# TIDA-010933-DCDC-HVGAN.net
KiCad netlist of a schematic drawn in Altium Designer
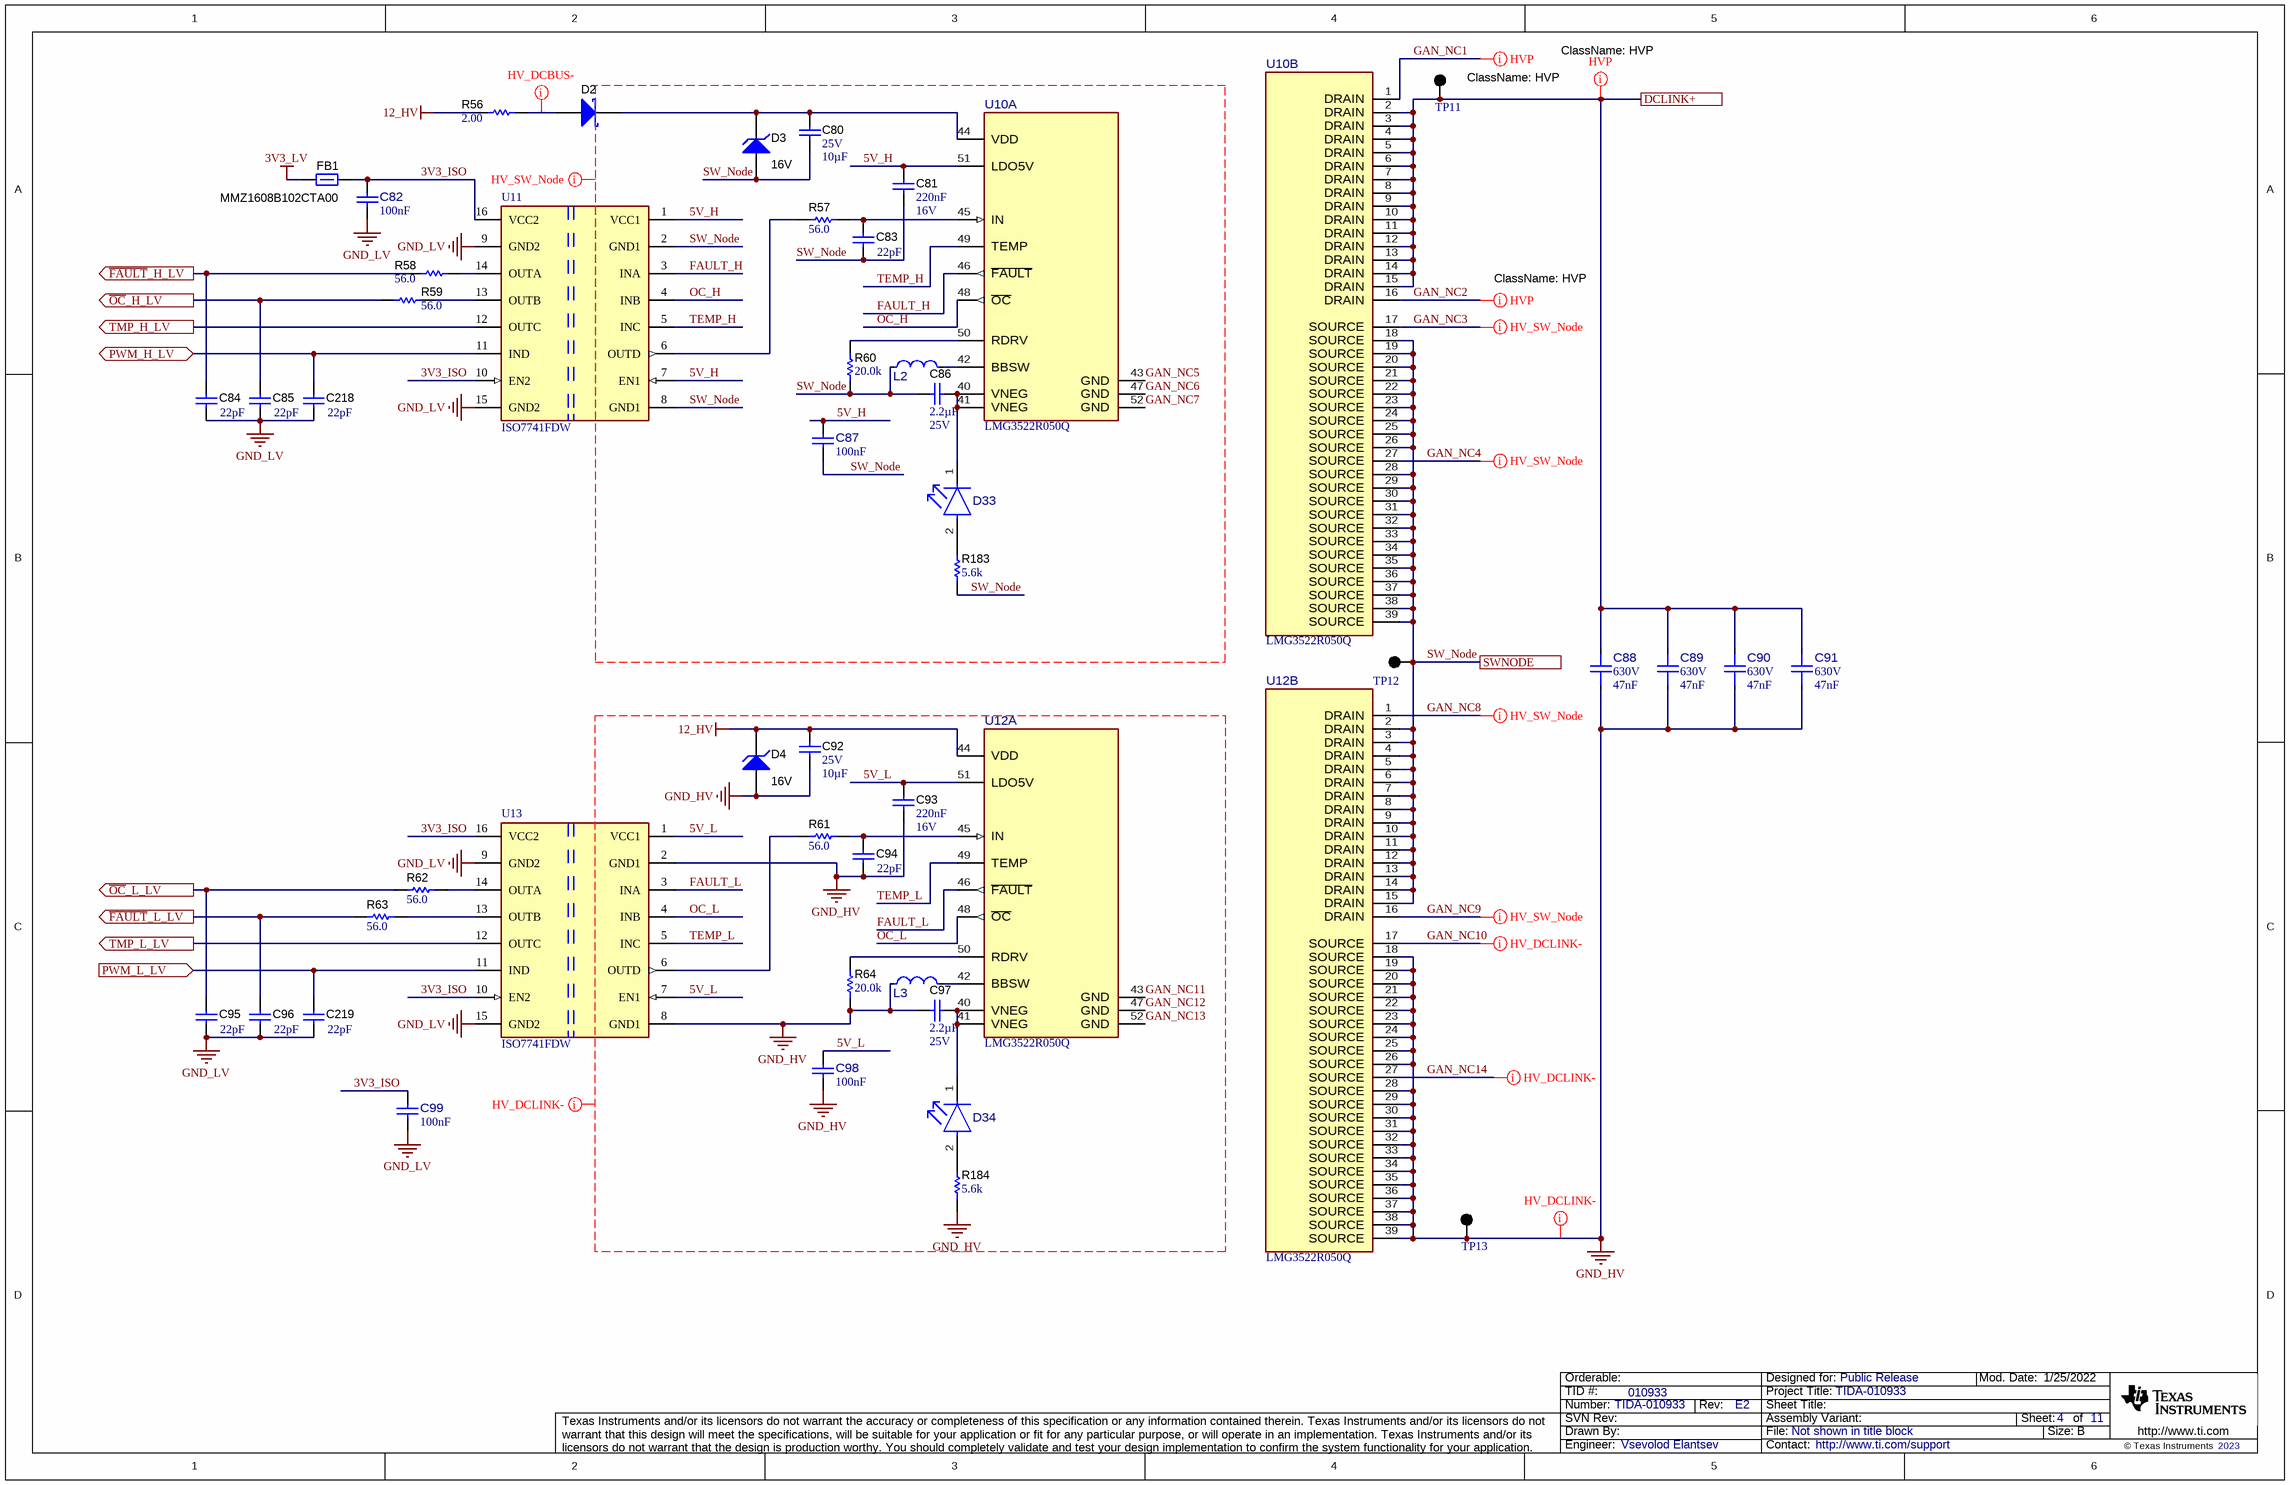
[diagram p0: TIDA-010933-DCDC-HVGAN.SchDoc]

(export (version "E")
  (design (tool "Eeschema 10.0.6"))
  (components
    (comp (ref "C80")
      (value "TMK316AB7106KLHT")
      (footprint "1206_180")
      (description "CAP, CERM, 10 µF, 25 V,+/- 10%, X7R, AEC-Q200 Grade 1, 1206")
      (fields
        (field (name "VDC_V") "25V")
        (field (name "MANUFACTURER") "Taiyo Yuden")
        (field (name "VALUEDISPLAYED") "10µF")
      )
      (libsource (lib "Altium Vault - TI") (part "Capacitor"))
    )
    (comp (ref "C81")
      (value "GRM188R71C224KA01D")
      (footprint "0603")
      (description "CAP, CERM, 0.22 uF, 16 V, +/- 10%, X7R, 0603")
      (fields
        (field (name "MANUFACTURER") "MuRata")
        (field (name "CAP_F") "220nF")
        (field (name "VDC_V") "16V")
        (field (name "PUBLISHER") "Texas Instruments")
      )
      (libsource (lib "Altium Vault - TI") (part "Capacitor"))
    )
    (comp (ref "C82")
      (value "CL10B104KB8NNNC")
      (footprint "FP-CL10B104KB8NNNC_0603-IPC_B")
      (description "CAP CER 0.1UF 50V X7R 0603")
      (fields (field (name "CAP_F") "100nF") (field (name "MANUFACTURER") "Samsung"))
      (libsource (lib "Altium Vault - TI") (part "SYM-CAPACITOR"))
    )
    (comp (ref "C83")
      (value "GRM1885C1H220JA01D")
      (footprint "0603")
      (description "CAP, CERM, 22 pF, 50 V, +/- 5%, C0G/NP0, 0603")
      (fields
        (field (name "MANUFACTURER") "MuRata")
        (field (name "VALUEDISPLAYED") "22pF")
        (field (name "PUBLISHER") "Texas Instruments")
      )
      (libsource (lib "Altium Vault - TI") (part "Capacitor"))
    )
    (comp (ref "C84")
      (value "GRM1885C1H220JA01D")
      (footprint "0603")
      (description "CAP, CERM, 22 pF, 50 V, +/- 5%, C0G/NP0, 0603")
      (fields
        (field (name "MANUFACTURER") "MuRata")
        (field (name "VALUEDISPLAYED") "22pF")
        (field (name "PUBLISHER") "Texas Instruments")
      )
      (libsource (lib "Altium Vault - TI") (part "Capacitor"))
    )
    (comp (ref "C85")
      (value "GRM1885C1H220JA01D")
      (footprint "0603")
      (description "CAP, CERM, 22 pF, 50 V, +/- 5%, C0G/NP0, 0603")
      (fields
        (field (name "MANUFACTURER") "MuRata")
        (field (name "VALUEDISPLAYED") "22pF")
        (field (name "PUBLISHER") "Texas Instruments")
      )
      (libsource (lib "Altium Vault - TI") (part "Capacitor"))
    )
    (comp (ref "C86")
      (value "CGA4J3X7R1E225K125AB")
      (footprint "0805_HV")
      (description "CAP, CERM, 2.2 uF, 25 V, +/- 10%, X7R, AEC-Q200 Grade 1, 0805")
      (fields
        (field (name "MANUFACTURER") "TDK")
        (field (name "CAP_F") "2.2µF")
        (field (name "VDC_V") "25V")
        (field (name "PUBLISHER") "Texas Instruments")
      )
      (libsource (lib "Altium Vault - TI") (part "Capacitor"))
    )
    (comp (ref "C87")
      (value "CL10B104KB8NNNC")
      (footprint "FP-CL10B104KB8NNNC_0603-IPC_B")
      (description "CAP CER 0.1UF 50V X7R 0603")
      (fields (field (name "CAP_F") "100nF") (field (name "MANUFACTURER") "Samsung"))
      (libsource (lib "Altium Vault - TI") (part "SYM-CAPACITOR"))
    )
    (comp (ref "C88")
      (value "C4532C0G2J473J320KA")
      (footprint "FP-C4532C0G2J473J320KA_1812-MFG")
      (description "C Series 1812 0.047 uF 630 V ±5% Tolerance C0G/NP0 Multilayer Ceramic Capacitor")
      (fields
        (field (name "DIGIKEY PART NUMBER") "445-14979-1-ND")
        (field (name "MANUFACTURER") "TDK")
        (field (name "VDC_V") "630V")
        (field (name "VALUEDISPLAYED") "47nF")
      )
      (libsource (lib "Altium Vault - TI") (part "SYM-C4532C0G2J473J320KA"))
    )
    (comp (ref "C89")
      (value "C4532C0G2J473J320KA")
      (footprint "FP-C4532C0G2J473J320KA_1812-MFG")
      (description "C Series 1812 0.047 uF 630 V ±5% Tolerance C0G/NP0 Multilayer Ceramic Capacitor")
      (fields
        (field (name "DIGIKEY PART NUMBER") "445-14979-1-ND")
        (field (name "MANUFACTURER") "TDK")
        (field (name "VDC_V") "630V")
        (field (name "VALUEDISPLAYED") "47nF")
      )
      (libsource (lib "Altium Vault - TI") (part "SYM-C4532C0G2J473J320KA"))
    )
    (comp (ref "C90")
      (value "C4532C0G2J473J320KA")
      (footprint "FP-C4532C0G2J473J320KA_1812-MFG")
      (description "C Series 1812 0.047 uF 630 V ±5% Tolerance C0G/NP0 Multilayer Ceramic Capacitor")
      (fields
        (field (name "DIGIKEY PART NUMBER") "445-14979-1-ND")
        (field (name "MANUFACTURER") "TDK")
        (field (name "VDC_V") "630V")
        (field (name "VALUEDISPLAYED") "47nF")
      )
      (libsource (lib "Altium Vault - TI") (part "SYM-C4532C0G2J473J320KA"))
    )
    (comp (ref "C91")
      (value "C4532C0G2J473J320KA")
      (footprint "FP-C4532C0G2J473J320KA_1812-MFG")
      (description "C Series 1812 0.047 uF 630 V ±5% Tolerance C0G/NP0 Multilayer Ceramic Capacitor")
      (fields
        (field (name "DIGIKEY PART NUMBER") "445-14979-1-ND")
        (field (name "MANUFACTURER") "TDK")
        (field (name "VDC_V") "630V")
        (field (name "VALUEDISPLAYED") "47nF")
      )
      (libsource (lib "Altium Vault - TI") (part "SYM-C4532C0G2J473J320KA"))
    )
    (comp (ref "C92")
      (value "TMK316AB7106KLHT")
      (footprint "1206_180")
      (description "CAP, CERM, 10 µF, 25 V,+/- 10%, X7R, AEC-Q200 Grade 1, 1206")
      (fields
        (field (name "VDC_V") "25V")
        (field (name "MANUFACTURER") "Taiyo Yuden")
        (field (name "VALUEDISPLAYED") "10µF")
      )
      (libsource (lib "Altium Vault - TI") (part "Capacitor"))
    )
    (comp (ref "C93")
      (value "GRM188R71C224KA01D")
      (footprint "0603")
      (description "CAP, CERM, 0.22 uF, 16 V, +/- 10%, X7R, 0603")
      (fields
        (field (name "MANUFACTURER") "MuRata")
        (field (name "CAP_F") "220nF")
        (field (name "VDC_V") "16V")
        (field (name "PUBLISHER") "Texas Instruments")
      )
      (libsource (lib "Altium Vault - TI") (part "Capacitor"))
    )
    (comp (ref "C94")
      (value "GRM1885C1H220JA01D")
      (footprint "0603")
      (description "CAP, CERM, 22 pF, 50 V, +/- 5%, C0G/NP0, 0603")
      (fields
        (field (name "MANUFACTURER") "MuRata")
        (field (name "VALUEDISPLAYED") "22pF")
        (field (name "PUBLISHER") "Texas Instruments")
      )
      (libsource (lib "Altium Vault - TI") (part "Capacitor"))
    )
    (comp (ref "C95")
      (value "GRM1885C1H220JA01D")
      (footprint "0603")
      (description "CAP, CERM, 22 pF, 50 V, +/- 5%, C0G/NP0, 0603")
      (fields
        (field (name "MANUFACTURER") "MuRata")
        (field (name "VALUEDISPLAYED") "22pF")
        (field (name "PUBLISHER") "Texas Instruments")
      )
      (libsource (lib "Altium Vault - TI") (part "Capacitor"))
    )
    (comp (ref "C96")
      (value "GRM1885C1H220JA01D")
      (footprint "0603")
      (description "CAP, CERM, 22 pF, 50 V, +/- 5%, C0G/NP0, 0603")
      (fields
        (field (name "MANUFACTURER") "MuRata")
        (field (name "VALUEDISPLAYED") "22pF")
        (field (name "PUBLISHER") "Texas Instruments")
      )
      (libsource (lib "Altium Vault - TI") (part "Capacitor"))
    )
    (comp (ref "C97")
      (value "CGA4J3X7R1E225K125AB")
      (footprint "0805_HV")
      (description "CAP, CERM, 2.2 uF, 25 V, +/- 10%, X7R, AEC-Q200 Grade 1, 0805")
      (fields
        (field (name "MANUFACTURER") "TDK")
        (field (name "CAP_F") "2.2µF")
        (field (name "VDC_V") "25V")
        (field (name "PUBLISHER") "Texas Instruments")
      )
      (libsource (lib "Altium Vault - TI") (part "Capacitor"))
    )
    (comp (ref "C98")
      (value "CL10B104KB8NNNC")
      (footprint "FP-CL10B104KB8NNNC_0603-IPC_B")
      (description "CAP CER 0.1UF 50V X7R 0603")
      (fields (field (name "CAP_F") "100nF") (field (name "MANUFACTURER") "Samsung"))
      (libsource (lib "Altium Vault - TI") (part "SYM-CAPACITOR"))
    )
    (comp (ref "C99")
      (value "CL10B104KB8NNNC")
      (footprint "FP-CL10B104KB8NNNC_0603-IPC_B")
      (description "CAP CER 0.1UF 50V X7R 0603")
      (fields (field (name "CAP_F") "100nF") (field (name "MANUFACTURER") "Samsung"))
      (libsource (lib "Altium Vault - TI") (part "SYM-CAPACITOR"))
    )
    (comp (ref "C218")
      (value "GRM1885C1H220JA01D")
      (footprint "0603")
      (description "CAP, CERM, 22 pF, 50 V, +/- 5%, C0G/NP0, 0603")
      (fields
        (field (name "MANUFACTURER") "MuRata")
        (field (name "VALUEDISPLAYED") "22pF")
        (field (name "PUBLISHER") "Texas Instruments")
      )
      (libsource (lib "Altium Vault - TI") (part "Capacitor"))
    )
    (comp (ref "C219")
      (value "GRM1885C1H220JA01D")
      (footprint "0603")
      (description "CAP, CERM, 22 pF, 50 V, +/- 5%, C0G/NP0, 0603")
      (fields
        (field (name "MANUFACTURER") "MuRata")
        (field (name "VALUEDISPLAYED") "22pF")
        (field (name "PUBLISHER") "Texas Instruments")
      )
      (libsource (lib "Altium Vault - TI") (part "Capacitor"))
    )
    (comp (ref "D2")
      (value "GB01SLT06-214")
      (footprint "SMB")
      (description "Diode, Schottky, 650 V, 1 A, SMB")
      (fields (field (name "MANUFACTURER") "GeneSiC Semiconductor"))
      (libsource (lib "Altium Vault - TI") (part "DIODE_SCHOTTKY"))
    )
    (comp (ref "D3")
      (value "16V")
      (footprint "SOD-123")
      (description "Diode, Zener, 16 V, 500 mW, AEC-Q101, SOD-123")
      (fields (field (name "PARTNUMBER") "BZT52C16-7-F") (field (name "MANUFACTURER") "Diodes Inc."))
      (libsource (lib "Altium Vault - TI") (part "Zener"))
    )
    (comp (ref "D4")
      (value "16V")
      (footprint "SOD-123")
      (description "Diode, Zener, 16 V, 500 mW, AEC-Q101, SOD-123")
      (fields (field (name "PARTNUMBER") "BZT52C16-7-F") (field (name "MANUFACTURER") "Diodes Inc."))
      (libsource (lib "Altium Vault - TI") (part "Zener"))
    )
    (comp (ref "D33")
      (value "KG DELLS1.22-JGKH-24")
      (footprint "FP-KG DELLS1.22-JGKH-24_0603-MFG")
      (description "Standard LEDs - SMD Green TOPLED E 1608")
      (fields
        (field (name "MANUFACTURER") "Osram Opto")
        (field (name "MOUSER PART NUMBER") "720-KGDELLS122A4849")
      )
      (libsource (lib "Altium Vault - TI") (part "SYM-KG DELLS1.22-JGKH-24"))
    )
    (comp (ref "D34")
      (value "KG DELLS1.22-JGKH-24")
      (footprint "FP-KG DELLS1.22-JGKH-24_0603-MFG")
      (description "Standard LEDs - SMD Green TOPLED E 1608")
      (fields
        (field (name "MANUFACTURER") "Osram Opto")
        (field (name "MOUSER PART NUMBER") "720-KGDELLS122A4849")
      )
      (libsource (lib "Altium Vault - TI") (part "SYM-KG DELLS1.22-JGKH-24"))
    )
    (comp (ref "FB1")
      (value "MMZ1608B102CTA00")
      (footprint "MMZ1608_095")
      (description "Ferrite Bead, 1000 ohm @ 100 MHz, 0.3 A, 0603")
      (fields (field (name "MANUFACTURER") "TDK") (field (name "PUBLISHER") "Texas Instruments"))
      (libsource (lib "Altium Vault - TI") (part "Ferrite_Bead"))
    )
    (comp (ref "L2")
      (value "SDEM20161T-4R7MS")
      (footprint "FP-SDEM20161T-4R7MS_SMD2-MFG")
      (description "4.7µH Unshielded Inductor 1.1A 426mOhm Max 0806 (2016 Metric)")
      (fields
        (field (name "MANUFACTURER") "Cyntec")
        (field (name "DIGIKEY PART NUMBER") "2037-SDEM20161T-4R7MSCT-ND")
      )
      (libsource (lib "Altium Vault - TI") (part "SYM-SDEM20161T-4R7MS"))
    )
    (comp (ref "L3")
      (value "SDEM20161T-4R7MS")
      (footprint "FP-SDEM20161T-4R7MS_SMD2-MFG")
      (description "4.7µH Unshielded Inductor 1.1A 426mOhm Max 0806 (2016 Metric)")
      (fields
        (field (name "MANUFACTURER") "Cyntec")
        (field (name "DIGIKEY PART NUMBER") "2037-SDEM20161T-4R7MSCT-ND")
      )
      (libsource (lib "Altium Vault - TI") (part "SYM-SDEM20161T-4R7MS"))
    )
    (comp (ref "R56")
      (value "CRCW08052R00FKEA")
      (footprint "0805_HV")
      (description "RES, 2.00, 1%, 0.125 W, AEC-Q200 Grade 0, 0805")
      (fields (field (name "MANUFACTURER") "Vishay-Dale") (field (name "VALUEDISPLAYED") "2.00"))
      (libsource (lib "Altium Vault - TI") (part "Resistor"))
    )
    (comp (ref "R57")
      (value "RC0603FR-0756RL")
      (footprint "0603")
      (description "RES, 56.0, 1%, 0.1 W, 0603")
      (fields (field (name "MANUFACTURER") "Yageo") (field (name "VALUEDISPLAYED") "56.0"))
      (libsource (lib "Altium Vault - TI") (part "Resistor"))
    )
    (comp (ref "R58")
      (value "RC0603FR-0756RL")
      (footprint "0603")
      (description "RES, 56.0, 1%, 0.1 W, 0603")
      (fields (field (name "MANUFACTURER") "Yageo") (field (name "VALUEDISPLAYED") "56.0"))
      (libsource (lib "Altium Vault - TI") (part "Resistor"))
    )
    (comp (ref "R59")
      (value "RC0603FR-0756RL")
      (footprint "0603")
      (description "RES, 56.0, 1%, 0.1 W, 0603")
      (fields (field (name "MANUFACTURER") "Yageo") (field (name "VALUEDISPLAYED") "56.0"))
      (libsource (lib "Altium Vault - TI") (part "Resistor"))
    )
    (comp (ref "R60")
      (value "RC0603FR-0720KL")
      (footprint "0603")
      (description "RES, 20.0 k, 1%, 0.1 W, 0603")
      (fields (field (name "MANUFACTURER") "Yageo") (field (name "VALUEDISPLAYED") "20.0k"))
      (libsource (lib "Altium Vault - TI") (part "Resistor"))
    )
    (comp (ref "R61")
      (value "RC0603FR-0756RL")
      (footprint "0603")
      (description "RES, 56.0, 1%, 0.1 W, 0603")
      (fields (field (name "MANUFACTURER") "Yageo") (field (name "VALUEDISPLAYED") "56.0"))
      (libsource (lib "Altium Vault - TI") (part "Resistor"))
    )
    (comp (ref "R62")
      (value "RC0603FR-0756RL")
      (footprint "0603")
      (description "RES, 56.0, 1%, 0.1 W, 0603")
      (fields (field (name "MANUFACTURER") "Yageo") (field (name "VALUEDISPLAYED") "56.0"))
      (libsource (lib "Altium Vault - TI") (part "Resistor"))
    )
    (comp (ref "R63")
      (value "RC0603FR-0756RL")
      (footprint "0603")
      (description "RES, 56.0, 1%, 0.1 W, 0603")
      (fields (field (name "MANUFACTURER") "Yageo") (field (name "VALUEDISPLAYED") "56.0"))
      (libsource (lib "Altium Vault - TI") (part "Resistor"))
    )
    (comp (ref "R64")
      (value "RC0603FR-0720KL")
      (footprint "0603")
      (description "RES, 20.0 k, 1%, 0.1 W, 0603")
      (fields (field (name "MANUFACTURER") "Yageo") (field (name "VALUEDISPLAYED") "20.0k"))
      (libsource (lib "Altium Vault - TI") (part "Resistor"))
    )
    (comp (ref "R183")
      (value "RC0603JR-075K6L")
      (footprint "0603")
      (description "RES, 5.6 k, 5%, 0.1 W, 0603")
      (fields (field (name "MANUFACTURER") "Yageo") (field (name "VALUEDISPLAYED") "5.6k"))
      (libsource (lib "Altium Vault - TI") (part "Resistor"))
    )
    (comp (ref "R184")
      (value "RC0603JR-075K6L")
      (footprint "0603")
      (description "RES, 5.6 k, 5%, 0.1 W, 0603")
      (fields (field (name "MANUFACTURER") "Yageo") (field (name "VALUEDISPLAYED") "5.6k"))
      (libsource (lib "Altium Vault - TI") (part "Resistor"))
    )
    (comp (ref "TP11")
      (value "5001")
      (footprint "Keystone5001")
      (description "Test Point, Miniature, Black, TH")
      (fields
        (field (name "MANUFACTURER") "Keystone Electronics")
        (field (name "PUBLISHER") "Texas Instruments")
      )
      (libsource (lib "Altium Vault - TI") (part "5001"))
    )
    (comp (ref "TP12")
      (value "5001")
      (footprint "Keystone5001")
      (description "Test Point, Miniature, Black, TH")
      (fields
        (field (name "MANUFACTURER") "Keystone Electronics")
        (field (name "PUBLISHER") "Texas Instruments")
      )
      (libsource (lib "Altium Vault - TI") (part "5001"))
    )
    (comp (ref "TP13")
      (value "5001")
      (footprint "Keystone5001")
      (description "Test Point, Miniature, Black, TH")
      (fields
        (field (name "MANUFACTURER") "Keystone Electronics")
        (field (name "PUBLISHER") "Texas Instruments")
      )
      (libsource (lib "Altium Vault - TI") (part "5001"))
    )
    (comp (ref "U10")
      (value "LMG3522R030Q")
      (footprint "RQS0052C-C01-MFG")
      (description "650-V 30-mΩ GaN FET with Integrated Driver and Protection")
      (fields
        (field (name "PARTNUMBER") "LMG3522R050Q")
        (field (name "MANUFACTURER") "Texas Instruments")
        (field (name "PART NUMBER") "LMG3522R050Q")
      )
      (libsource (lib "Altium Vault - TI") (part "SYM-LMG3522R030Q"))
    )
    (comp (ref "U11")
      (value "ISO7741FDW")
      (footprint "FP-DW0016A-IPC_A")
      (description "DGTL ISO 5000VRMS 4CH GP 16SOIC")
      (fields (field (name "MANUFACTURER") "Texas Instruments"))
      (libsource (lib "Altium Content Vault") (part "37cc8613f039a50342d8adde8bb14cd"))
    )
    (comp (ref "U12")
      (value "LMG3522R030Q")
      (footprint "RQS0052C-C01-MFG")
      (description "650-V 30-mΩ GaN FET with Integrated Driver and Protection")
      (fields
        (field (name "PARTNUMBER") "LMG3522R050Q")
        (field (name "MANUFACTURER") "Texas Instruments")
        (field (name "PART NUMBER") "LMG3522R050Q")
      )
      (libsource (lib "Altium Vault - TI") (part "SYM-LMG3522R030Q"))
    )
    (comp (ref "U13")
      (value "ISO7741FDW")
      (footprint "FP-DW0016A-IPC_A")
      (description "DGTL ISO 5000VRMS 4CH GP 16SOIC")
      (fields (field (name "MANUFACTURER") "Texas Instruments"))
      (libsource (lib "Altium Content Vault") (part "37cc8613f039a50342d8adde8bb14cd"))
    )
  )
  (nets
    (net (code "1") (name "/3V3_ISO") (class "Default")
      (node (ref "C82") (pin "1") (pinfunction "1_1") (pintype "passive"))
      (node (ref "C99") (pin "1") (pinfunction "1_1") (pintype "passive"))
      (node (ref "FB1") (pin "2") (pinfunction "2_2") (pintype "passive"))
      (node (ref "U11") (pin "10") (pinfunction "EN2_10") (pintype "input"))
      (node (ref "U11") (pin "16") (pinfunction "VCC2_16") (pintype "power_in"))
      (node (ref "U13") (pin "10") (pinfunction "EN2_10") (pintype "input"))
      (node (ref "U13") (pin "16") (pinfunction "VCC2_16") (pintype "power_in"))
    )
    (net (code "2") (name "/5V_H") (class "Default")
      (node (ref "C81") (pin "1") (pinfunction "1_1") (pintype "passive"))
      (node (ref "C87") (pin "1") (pinfunction "1_1") (pintype "passive"))
      (node (ref "U10") (pin "51") (pinfunction "LDO5V_51") (pintype "power_in"))
      (node (ref "U11") (pin "1") (pinfunction "VCC1_1") (pintype "power_in"))
      (node (ref "U11") (pin "7") (pinfunction "EN1_7") (pintype "input"))
    )
    (net (code "3") (name "/5V_L") (class "Default")
      (node (ref "C93") (pin "1") (pinfunction "1_1") (pintype "passive"))
      (node (ref "C98") (pin "1") (pinfunction "1_1") (pintype "passive"))
      (node (ref "U12") (pin "51") (pinfunction "LDO5V_51") (pintype "power_in"))
      (node (ref "U13") (pin "1") (pinfunction "VCC1_1") (pintype "power_in"))
      (node (ref "U13") (pin "7") (pinfunction "EN1_7") (pintype "input"))
    )
    (net (code "4") (name "/DCLINK+") (class "Default")
      (node (ref "C88") (pin "2") (pinfunction "2_2") (pintype "passive"))
      (node (ref "C89") (pin "2") (pinfunction "2_2") (pintype "passive"))
      (node (ref "C90") (pin "2") (pinfunction "2_2") (pintype "passive"))
      (node (ref "C91") (pin "2") (pinfunction "2_2") (pintype "passive"))
      (node (ref "TP11") (pin "1") (pintype "passive"))
      (node (ref "U10") (pin "10") (pinfunction "DRAIN_10") (pintype "passive"))
      (node (ref "U10") (pin "11") (pinfunction "DRAIN_11") (pintype "passive"))
      (node (ref "U10") (pin "12") (pinfunction "DRAIN_12") (pintype "passive"))
      (node (ref "U10") (pin "13") (pinfunction "DRAIN_13") (pintype "passive"))
      (node (ref "U10") (pin "14") (pinfunction "DRAIN_14") (pintype "passive"))
      (node (ref "U10") (pin "15") (pinfunction "DRAIN_15") (pintype "passive"))
      (node (ref "U10") (pin "2") (pinfunction "DRAIN_2") (pintype "passive"))
      (node (ref "U10") (pin "3") (pinfunction "DRAIN_3") (pintype "passive"))
      (node (ref "U10") (pin "4") (pinfunction "DRAIN_4") (pintype "passive"))
      (node (ref "U10") (pin "5") (pinfunction "DRAIN_5") (pintype "passive"))
      (node (ref "U10") (pin "6") (pinfunction "DRAIN_6") (pintype "passive"))
      (node (ref "U10") (pin "7") (pinfunction "DRAIN_7") (pintype "passive"))
      (node (ref "U10") (pin "8") (pinfunction "DRAIN_8") (pintype "passive"))
      (node (ref "U10") (pin "9") (pinfunction "DRAIN_9") (pintype "passive"))
    )
    (net (code "5") (name "/FAULT_H") (class "Default")
      (node (ref "U10") (pin "46") (pinfunction "~{FAULT}_46") (pintype "output"))
      (node (ref "U11") (pin "3") (pinfunction "INA_3") (pintype "tri_state"))
    )
    (net (code "6") (name "/FAULT_L") (class "Default")
      (node (ref "U12") (pin "46") (pinfunction "~{FAULT}_46") (pintype "output"))
      (node (ref "U13") (pin "3") (pinfunction "INA_3") (pintype "tri_state"))
    )
    (net (code "7") (name "/GAN_NC1") (class "Default")
      (node (ref "U10") (pin "1") (pinfunction "DRAIN_1") (pintype "passive"))
    )
    (net (code "8") (name "/GAN_NC2") (class "Default")
      (node (ref "U10") (pin "16") (pinfunction "DRAIN_16") (pintype "passive"))
    )
    (net (code "9") (name "/GAN_NC3") (class "Default")
      (node (ref "U10") (pin "17") (pinfunction "SOURCE_17") (pintype "passive"))
    )
    (net (code "10") (name "/GAN_NC4") (class "Default")
      (node (ref "U10") (pin "27") (pinfunction "SOURCE_27") (pintype "passive"))
    )
    (net (code "11") (name "/GAN_NC5") (class "Default")
      (node (ref "U10") (pin "43") (pinfunction "GND_43") (pintype "power_in"))
    )
    (net (code "12") (name "/GAN_NC6") (class "Default")
      (node (ref "U10") (pin "47") (pinfunction "GND_47") (pintype "power_in"))
    )
    (net (code "13") (name "/GAN_NC7") (class "Default")
      (node (ref "U10") (pin "52") (pinfunction "GND_52") (pintype "power_in"))
    )
    (net (code "14") (name "/GAN_NC8") (class "Default")
      (node (ref "U12") (pin "1") (pinfunction "DRAIN_1") (pintype "passive"))
    )
    (net (code "15") (name "/GAN_NC9") (class "Default")
      (node (ref "U12") (pin "16") (pinfunction "DRAIN_16") (pintype "passive"))
    )
    (net (code "16") (name "/GAN_NC10") (class "Default")
      (node (ref "U12") (pin "17") (pinfunction "SOURCE_17") (pintype "passive"))
    )
    (net (code "17") (name "/GAN_NC11") (class "Default")
      (node (ref "U12") (pin "43") (pinfunction "GND_43") (pintype "power_in"))
    )
    (net (code "18") (name "/GAN_NC12") (class "Default")
      (node (ref "U12") (pin "47") (pinfunction "GND_47") (pintype "power_in"))
    )
    (net (code "19") (name "/GAN_NC13") (class "Default")
      (node (ref "U12") (pin "52") (pinfunction "GND_52") (pintype "power_in"))
    )
    (net (code "20") (name "/GAN_NC14") (class "Default")
      (node (ref "U12") (pin "27") (pinfunction "SOURCE_27") (pintype "passive"))
    )
    (net (code "21") (name "/OC_H") (class "Default")
      (node (ref "U10") (pin "48") (pinfunction "~{OC}_48") (pintype "output"))
      (node (ref "U11") (pin "4") (pinfunction "INB_4") (pintype "tri_state"))
    )
    (net (code "22") (name "/OC_L") (class "Default")
      (node (ref "U12") (pin "48") (pinfunction "~{OC}_48") (pintype "output"))
      (node (ref "U13") (pin "4") (pinfunction "INB_4") (pintype "tri_state"))
    )
    (net (code "23") (name "/PWM_H_LV") (class "Default")
      (node (ref "C218") (pin "1") (pinfunction "1_1") (pintype "passive"))
      (node (ref "U11") (pin "11") (pinfunction "IND_11") (pintype "tri_state"))
    )
    (net (code "24") (name "/PWM_L_LV") (class "Default")
      (node (ref "C219") (pin "1") (pinfunction "1_1") (pintype "passive"))
      (node (ref "U13") (pin "11") (pinfunction "IND_11") (pintype "tri_state"))
    )
    (net (code "25") (name "/SW_Node") (class "Default")
      (node (ref "C80") (pin "2") (pinfunction "2_2") (pintype "passive"))
      (node (ref "C81") (pin "2") (pinfunction "2_2") (pintype "passive"))
      (node (ref "C83") (pin "2") (pinfunction "2_2") (pintype "passive"))
      (node (ref "C86") (pin "2") (pinfunction "2_2") (pintype "passive"))
      (node (ref "C87") (pin "2") (pinfunction "2_2") (pintype "passive"))
      (node (ref "D3") (pin "2") (pinfunction "A_2") (pintype "passive"))
      (node (ref "L2") (pin "1") (pinfunction "1_1") (pintype "passive"))
      (node (ref "R183") (pin "1") (pinfunction "1_1") (pintype "passive"))
      (node (ref "R60") (pin "1") (pinfunction "1_1") (pintype "passive"))
      (node (ref "TP12") (pin "1") (pintype "passive"))
      (node (ref "U10") (pin "18") (pinfunction "SOURCE_18") (pintype "passive"))
      (node (ref "U10") (pin "19") (pinfunction "SOURCE_19") (pintype "passive"))
      (node (ref "U10") (pin "20") (pinfunction "SOURCE_20") (pintype "passive"))
      (node (ref "U10") (pin "21") (pinfunction "SOURCE_21") (pintype "passive"))
      (node (ref "U10") (pin "22") (pinfunction "SOURCE_22") (pintype "passive"))
      (node (ref "U10") (pin "23") (pinfunction "SOURCE_23") (pintype "passive"))
      (node (ref "U10") (pin "24") (pinfunction "SOURCE_24") (pintype "passive"))
      (node (ref "U10") (pin "25") (pinfunction "SOURCE_25") (pintype "passive"))
      (node (ref "U10") (pin "26") (pinfunction "SOURCE_26") (pintype "passive"))
      (node (ref "U10") (pin "28") (pinfunction "SOURCE_28") (pintype "passive"))
      (node (ref "U10") (pin "29") (pinfunction "SOURCE_29") (pintype "passive"))
      (node (ref "U10") (pin "30") (pinfunction "SOURCE_30") (pintype "passive"))
      (node (ref "U10") (pin "31") (pinfunction "SOURCE_31") (pintype "passive"))
      (node (ref "U10") (pin "32") (pinfunction "SOURCE_32") (pintype "passive"))
      (node (ref "U10") (pin "33") (pinfunction "SOURCE_33") (pintype "passive"))
      (node (ref "U10") (pin "34") (pinfunction "SOURCE_34") (pintype "passive"))
      (node (ref "U10") (pin "35") (pinfunction "SOURCE_35") (pintype "passive"))
      (node (ref "U10") (pin "36") (pinfunction "SOURCE_36") (pintype "passive"))
      (node (ref "U10") (pin "37") (pinfunction "SOURCE_37") (pintype "passive"))
      (node (ref "U10") (pin "38") (pinfunction "SOURCE_38") (pintype "passive"))
      (node (ref "U10") (pin "39") (pinfunction "SOURCE_39") (pintype "passive"))
      (node (ref "U11") (pin "2") (pinfunction "GND1_2") (pintype "power_in"))
      (node (ref "U11") (pin "8") (pinfunction "GND1_8") (pintype "power_in"))
      (node (ref "U12") (pin "10") (pinfunction "DRAIN_10") (pintype "passive"))
      (node (ref "U12") (pin "11") (pinfunction "DRAIN_11") (pintype "passive"))
      (node (ref "U12") (pin "12") (pinfunction "DRAIN_12") (pintype "passive"))
      (node (ref "U12") (pin "13") (pinfunction "DRAIN_13") (pintype "passive"))
      (node (ref "U12") (pin "14") (pinfunction "DRAIN_14") (pintype "passive"))
      (node (ref "U12") (pin "15") (pinfunction "DRAIN_15") (pintype "passive"))
      (node (ref "U12") (pin "2") (pinfunction "DRAIN_2") (pintype "passive"))
      (node (ref "U12") (pin "3") (pinfunction "DRAIN_3") (pintype "passive"))
      (node (ref "U12") (pin "4") (pinfunction "DRAIN_4") (pintype "passive"))
      (node (ref "U12") (pin "5") (pinfunction "DRAIN_5") (pintype "passive"))
      (node (ref "U12") (pin "6") (pinfunction "DRAIN_6") (pintype "passive"))
      (node (ref "U12") (pin "7") (pinfunction "DRAIN_7") (pintype "passive"))
      (node (ref "U12") (pin "8") (pinfunction "DRAIN_8") (pintype "passive"))
      (node (ref "U12") (pin "9") (pinfunction "DRAIN_9") (pintype "passive"))
    )
    (net (code "26") (name "/TEMP_H") (class "Default")
      (node (ref "U10") (pin "49") (pinfunction "TEMP_49") (pintype "passive"))
      (node (ref "U11") (pin "5") (pinfunction "INC_5") (pintype "tri_state"))
    )
    (net (code "27") (name "/TEMP_L") (class "Default")
      (node (ref "U12") (pin "49") (pinfunction "TEMP_49") (pintype "passive"))
      (node (ref "U13") (pin "5") (pinfunction "INC_5") (pintype "tri_state"))
    )
    (net (code "28") (name "/TMP_H_LV") (class "Default")
      (node (ref "U11") (pin "12") (pinfunction "OUTC_12") (pintype "passive"))
    )
    (net (code "29") (name "/TMP_L_LV") (class "Default")
      (node (ref "U13") (pin "12") (pinfunction "OUTC_12") (pintype "passive"))
    )
    (net (code "30") (name "/~{FAULT}_H_LV") (class "Default")
      (node (ref "C84") (pin "1") (pinfunction "1_1") (pintype "passive"))
      (node (ref "R58") (pin "1") (pinfunction "1_1") (pintype "passive"))
    )
    (net (code "31") (name "/~{FAULT}_L_LV") (class "Default")
      (node (ref "C96") (pin "1") (pinfunction "1_1") (pintype "passive"))
      (node (ref "R63") (pin "1") (pinfunction "1_1") (pintype "passive"))
    )
    (net (code "32") (name "/~{OC}_H_LV") (class "Default")
      (node (ref "C85") (pin "1") (pinfunction "1_1") (pintype "passive"))
      (node (ref "R59") (pin "1") (pinfunction "1_1") (pintype "passive"))
    )
    (net (code "33") (name "/~{OC}_L_LV") (class "Default")
      (node (ref "C95") (pin "1") (pinfunction "1_1") (pintype "passive"))
      (node (ref "R62") (pin "1") (pinfunction "1_1") (pintype "passive"))
    )
    (net (code "34") (name "3V3_LV") (class "Default")
      (node (ref "FB1") (pin "1") (pinfunction "1_1") (pintype "passive"))
    )
    (net (code "35") (name "12_HV") (class "Default")
      (node (ref "C92") (pin "1") (pinfunction "1_1") (pintype "passive"))
      (node (ref "D4") (pin "1") (pinfunction "K_1") (pintype "passive"))
      (node (ref "R56") (pin "1") (pinfunction "1_1") (pintype "passive"))
      (node (ref "U12") (pin "44") (pinfunction "VDD_44") (pintype "power_in"))
    )
    (net (code "36") (name "GND_HV") (class "Default")
      (node (ref "C88") (pin "1") (pinfunction "1_1") (pintype "passive"))
      (node (ref "C89") (pin "1") (pinfunction "1_1") (pintype "passive"))
      (node (ref "C90") (pin "1") (pinfunction "1_1") (pintype "passive"))
      (node (ref "C91") (pin "1") (pinfunction "1_1") (pintype "passive"))
      (node (ref "C92") (pin "2") (pinfunction "2_2") (pintype "passive"))
      (node (ref "C93") (pin "2") (pinfunction "2_2") (pintype "passive"))
      (node (ref "C94") (pin "2") (pinfunction "2_2") (pintype "passive"))
      (node (ref "C97") (pin "2") (pinfunction "2_2") (pintype "passive"))
      (node (ref "C98") (pin "2") (pinfunction "2_2") (pintype "passive"))
      (node (ref "D4") (pin "2") (pinfunction "A_2") (pintype "passive"))
      (node (ref "L3") (pin "1") (pinfunction "1_1") (pintype "passive"))
      (node (ref "R184") (pin "1") (pinfunction "1_1") (pintype "passive"))
      (node (ref "R64") (pin "1") (pinfunction "1_1") (pintype "passive"))
      (node (ref "TP13") (pin "1") (pintype "passive"))
      (node (ref "U12") (pin "18") (pinfunction "SOURCE_18") (pintype "passive"))
      (node (ref "U12") (pin "19") (pinfunction "SOURCE_19") (pintype "passive"))
      (node (ref "U12") (pin "20") (pinfunction "SOURCE_20") (pintype "passive"))
      (node (ref "U12") (pin "21") (pinfunction "SOURCE_21") (pintype "passive"))
      (node (ref "U12") (pin "22") (pinfunction "SOURCE_22") (pintype "passive"))
      (node (ref "U12") (pin "23") (pinfunction "SOURCE_23") (pintype "passive"))
      (node (ref "U12") (pin "24") (pinfunction "SOURCE_24") (pintype "passive"))
      (node (ref "U12") (pin "25") (pinfunction "SOURCE_25") (pintype "passive"))
      (node (ref "U12") (pin "26") (pinfunction "SOURCE_26") (pintype "passive"))
      (node (ref "U12") (pin "28") (pinfunction "SOURCE_28") (pintype "passive"))
      (node (ref "U12") (pin "29") (pinfunction "SOURCE_29") (pintype "passive"))
      (node (ref "U12") (pin "30") (pinfunction "SOURCE_30") (pintype "passive"))
      (node (ref "U12") (pin "31") (pinfunction "SOURCE_31") (pintype "passive"))
      (node (ref "U12") (pin "32") (pinfunction "SOURCE_32") (pintype "passive"))
      (node (ref "U12") (pin "33") (pinfunction "SOURCE_33") (pintype "passive"))
      (node (ref "U12") (pin "34") (pinfunction "SOURCE_34") (pintype "passive"))
      (node (ref "U12") (pin "35") (pinfunction "SOURCE_35") (pintype "passive"))
      (node (ref "U12") (pin "36") (pinfunction "SOURCE_36") (pintype "passive"))
      (node (ref "U12") (pin "37") (pinfunction "SOURCE_37") (pintype "passive"))
      (node (ref "U12") (pin "38") (pinfunction "SOURCE_38") (pintype "passive"))
      (node (ref "U12") (pin "39") (pinfunction "SOURCE_39") (pintype "passive"))
      (node (ref "U13") (pin "2") (pinfunction "GND1_2") (pintype "power_in"))
      (node (ref "U13") (pin "8") (pinfunction "GND1_8") (pintype "power_in"))
    )
    (net (code "37") (name "GND_LV") (class "Default")
      (node (ref "C218") (pin "2") (pinfunction "2_2") (pintype "passive"))
      (node (ref "C219") (pin "2") (pinfunction "2_2") (pintype "passive"))
      (node (ref "C82") (pin "2") (pinfunction "2_2") (pintype "passive"))
      (node (ref "C84") (pin "2") (pinfunction "2_2") (pintype "passive"))
      (node (ref "C85") (pin "2") (pinfunction "2_2") (pintype "passive"))
      (node (ref "C95") (pin "2") (pinfunction "2_2") (pintype "passive"))
      (node (ref "C96") (pin "2") (pinfunction "2_2") (pintype "passive"))
      (node (ref "C99") (pin "2") (pinfunction "2_2") (pintype "passive"))
      (node (ref "U11") (pin "15") (pinfunction "GND2_15") (pintype "power_in"))
      (node (ref "U11") (pin "9") (pinfunction "GND2_9") (pintype "power_in"))
      (node (ref "U13") (pin "15") (pinfunction "GND2_15") (pintype "power_in"))
      (node (ref "U13") (pin "9") (pinfunction "GND2_9") (pintype "power_in"))
    )
    (net (code "38") (name "Net-(D2-A)") (class "Default")
      (node (ref "D2") (pin "2") (pinfunction "A_2") (pintype "passive"))
      (node (ref "R56") (pin "2") (pinfunction "2_2") (pintype "passive"))
    )
    (net (code "39") (name "Net-(D2-K)") (class "Default")
      (node (ref "C80") (pin "1") (pinfunction "1_1") (pintype "passive"))
      (node (ref "D2") (pin "1") (pinfunction "K_1") (pintype "passive"))
      (node (ref "D3") (pin "1") (pinfunction "K_1") (pintype "passive"))
      (node (ref "U10") (pin "44") (pinfunction "VDD_44") (pintype "power_in"))
    )
    (net (code "40") (name "Net-(D33-ANODE)") (class "Default")
      (node (ref "D33") (pin "2") (pinfunction "ANODE_2") (pintype "passive"))
      (node (ref "R183") (pin "2") (pinfunction "2_2") (pintype "passive"))
    )
    (net (code "41") (name "Net-(D33-CATHODE)") (class "Default")
      (node (ref "C86") (pin "1") (pinfunction "1_1") (pintype "passive"))
      (node (ref "D33") (pin "1") (pinfunction "CATHODE_1") (pintype "passive"))
      (node (ref "U10") (pin "40") (pinfunction "VNEG_40") (pintype "passive"))
      (node (ref "U10") (pin "41") (pinfunction "VNEG_41") (pintype "passive"))
    )
    (net (code "42") (name "Net-(D34-ANODE)") (class "Default")
      (node (ref "D34") (pin "2") (pinfunction "ANODE_2") (pintype "passive"))
      (node (ref "R184") (pin "2") (pinfunction "2_2") (pintype "passive"))
    )
    (net (code "43") (name "Net-(D34-CATHODE)") (class "Default")
      (node (ref "C97") (pin "1") (pinfunction "1_1") (pintype "passive"))
      (node (ref "D34") (pin "1") (pinfunction "CATHODE_1") (pintype "passive"))
      (node (ref "U12") (pin "40") (pinfunction "VNEG_40") (pintype "passive"))
      (node (ref "U12") (pin "41") (pinfunction "VNEG_41") (pintype "passive"))
    )
    (net (code "44") (name "Net-(U10A-BBSW)") (class "Default")
      (node (ref "L2") (pin "2") (pinfunction "2_2") (pintype "passive"))
      (node (ref "U10") (pin "42") (pinfunction "BBSW_42") (pintype "passive"))
    )
    (net (code "45") (name "Net-(U10A-IN)") (class "Default")
      (node (ref "C83") (pin "1") (pinfunction "1_1") (pintype "passive"))
      (node (ref "R57") (pin "2") (pinfunction "2_2") (pintype "passive"))
      (node (ref "U10") (pin "45") (pinfunction "IN_45") (pintype "input"))
    )
    (net (code "46") (name "Net-(U10A-RDRV)") (class "Default")
      (node (ref "R60") (pin "2") (pinfunction "2_2") (pintype "passive"))
      (node (ref "U10") (pin "50") (pinfunction "RDRV_50") (pintype "passive"))
    )
    (net (code "47") (name "Net-(U11-OUTA)") (class "Default")
      (node (ref "R58") (pin "2") (pinfunction "2_2") (pintype "passive"))
      (node (ref "U11") (pin "14") (pinfunction "OUTA_14") (pintype "passive"))
    )
    (net (code "48") (name "Net-(U11-OUTB)") (class "Default")
      (node (ref "R59") (pin "2") (pinfunction "2_2") (pintype "passive"))
      (node (ref "U11") (pin "13") (pinfunction "OUTB_13") (pintype "passive"))
    )
    (net (code "49") (name "Net-(U11-OUTD)") (class "Default")
      (node (ref "R57") (pin "1") (pinfunction "1_1") (pintype "passive"))
      (node (ref "U11") (pin "6") (pinfunction "OUTD_6") (pintype "output"))
    )
    (net (code "50") (name "Net-(U12A-BBSW)") (class "Default")
      (node (ref "L3") (pin "2") (pinfunction "2_2") (pintype "passive"))
      (node (ref "U12") (pin "42") (pinfunction "BBSW_42") (pintype "passive"))
    )
    (net (code "51") (name "Net-(U12A-IN)") (class "Default")
      (node (ref "C94") (pin "1") (pinfunction "1_1") (pintype "passive"))
      (node (ref "R61") (pin "2") (pinfunction "2_2") (pintype "passive"))
      (node (ref "U12") (pin "45") (pinfunction "IN_45") (pintype "input"))
    )
    (net (code "52") (name "Net-(U12A-RDRV)") (class "Default")
      (node (ref "R64") (pin "2") (pinfunction "2_2") (pintype "passive"))
      (node (ref "U12") (pin "50") (pinfunction "RDRV_50") (pintype "passive"))
    )
    (net (code "53") (name "Net-(U13-OUTA)") (class "Default")
      (node (ref "R62") (pin "2") (pinfunction "2_2") (pintype "passive"))
      (node (ref "U13") (pin "14") (pinfunction "OUTA_14") (pintype "passive"))
    )
    (net (code "54") (name "Net-(U13-OUTB)") (class "Default")
      (node (ref "R63") (pin "2") (pinfunction "2_2") (pintype "passive"))
      (node (ref "U13") (pin "13") (pinfunction "OUTB_13") (pintype "passive"))
    )
    (net (code "55") (name "Net-(U13-OUTD)") (class "Default")
      (node (ref "R61") (pin "1") (pinfunction "1_1") (pintype "passive"))
      (node (ref "U13") (pin "6") (pinfunction "OUTD_6") (pintype "output"))
    )
  )
)
